# Battery_ECU.net
KiCad netlist of a schematic drawn in Altium Designer
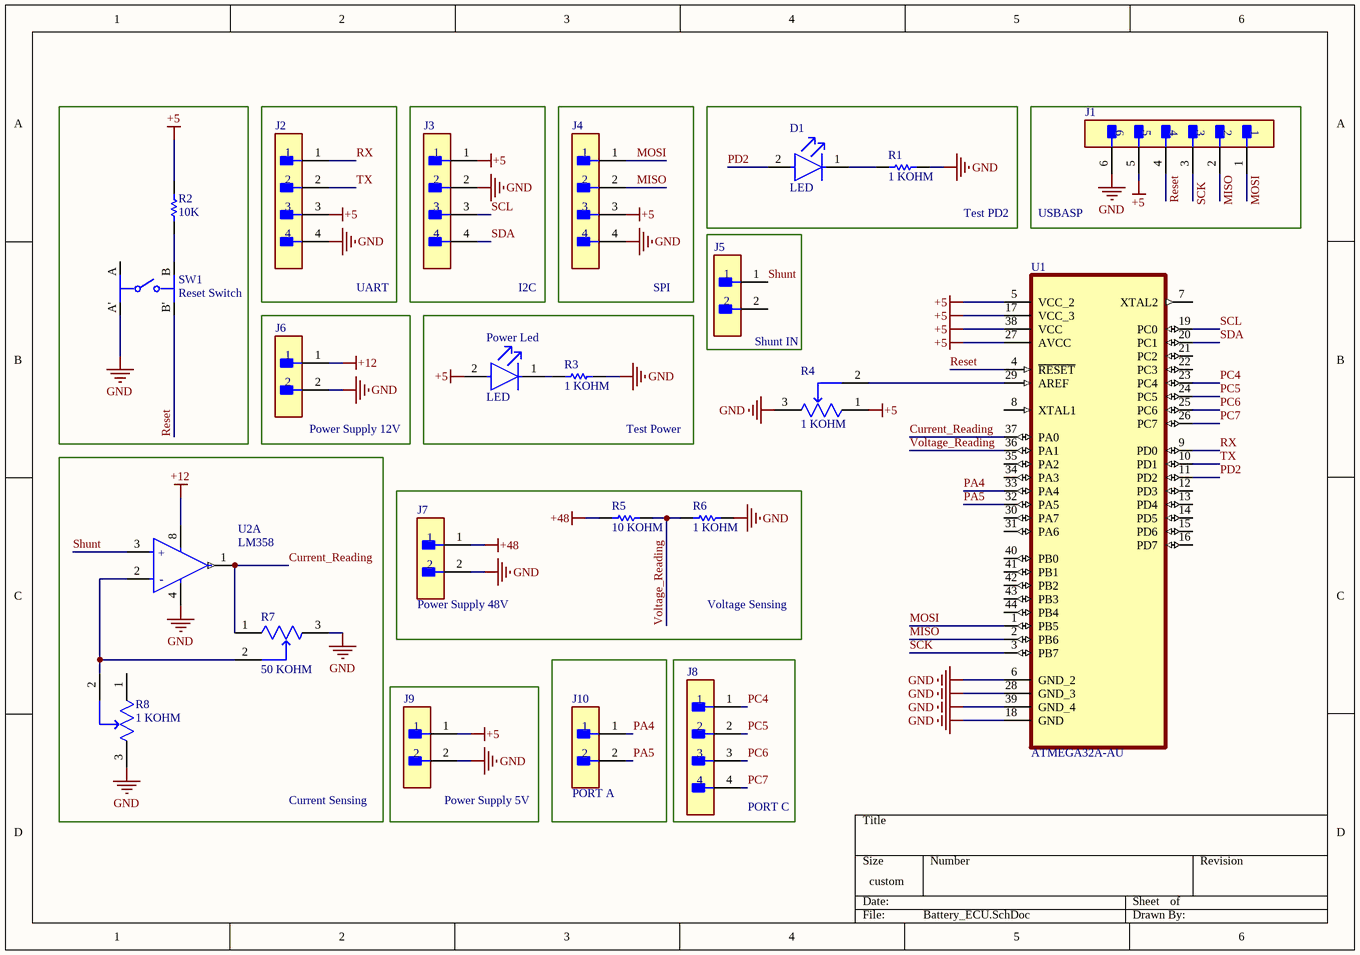
[diagram p0: Battery_ECU.SchDoc]

(export (version "E")
  (design (tool "Eeschema 10.0.6"))
  (components
    (comp (ref "D1")
      (value "LED")
      (footprint "FP-LTST-C171GKT-MFG")
      (description "LED GREEN CLEAR CHIP SMD")
      (libsource (lib "Altium Content Vault") (part "8706943c75ba83719d021d2fdc84c58"))
    )
    (comp (ref "J1")
      (value "USBASP")
      (footprint "FP-B6B-EH-A_LF_SN-MFG")
      (description "CONN HEADER VERT 6POS 2.5MM")
      (libsource (lib "Altium Content Vault") (part "f2cb566baf1c37ab5a3b8e90bbeafd6"))
    )
    (comp (ref "J2")
      (value "UART")
      (footprint "FP-B04B-XASK-1_LF_SN-MFG")
      (description "CONN HEADER VERT 4POS 2.5MM")
      (fields
        (field (name "OCTOPART") "https://octopart.com/b04b-xask-1%28lf%29%28sn%29-jst-3990149")
        (field (name "MANUFACTURER PART NUMBER") "B04B-XASK-1(LF)(SN)")
      )
      (libsource (lib "Altium Content Vault") (part "299a8cea1bdcbc3624fe62c390fa72c"))
    )
    (comp (ref "J3")
      (value "I2C")
      (footprint "FP-B04B-XASK-1_LF_SN-MFG")
      (description "CONN HEADER VERT 4POS 2.5MM")
      (fields
        (field (name "OCTOPART") "https://octopart.com/b04b-xask-1%28lf%29%28sn%29-jst-3990149")
        (field (name "MANUFACTURER PART NUMBER") "B04B-XASK-1(LF)(SN)")
      )
      (libsource (lib "Altium Content Vault") (part "299a8cea1bdcbc3624fe62c390fa72c"))
    )
    (comp (ref "J4")
      (value "SPI")
      (footprint "FP-B04B-XASK-1_LF_SN-MFG")
      (description "CONN HEADER VERT 4POS 2.5MM")
      (fields
        (field (name "OCTOPART") "https://octopart.com/b04b-xask-1%28lf%29%28sn%29-jst-3990149")
        (field (name "MANUFACTURER PART NUMBER") "B04B-XASK-1(LF)(SN)")
      )
      (libsource (lib "Altium Content Vault") (part "299a8cea1bdcbc3624fe62c390fa72c"))
    )
    (comp (ref "J5")
      (value "Shunt IN")
      (footprint "FP-B2B-XH-A_LF_SN-MFG")
      (description "CONN HEADER VERT 2POS 2.5MM")
      (libsource (lib "Altium Content Vault") (part "3bc925449376181038e59eaffc5286c"))
    )
    (comp (ref "J6")
      (value "Power Supply 12V")
      (footprint "FP-B2B-XH-A_LF_SN-MFG")
      (description "CONN HEADER VERT 2POS 2.5MM")
      (libsource (lib "Altium Content Vault") (part "3bc925449376181038e59eaffc5286c"))
    )
    (comp (ref "J7")
      (value "Power Supply 48V")
      (footprint "FP-B2B-XH-A_LF_SN-MFG")
      (description "CONN HEADER VERT 2POS 2.5MM")
      (libsource (lib "Altium Content Vault") (part "3bc925449376181038e59eaffc5286c"))
    )
    (comp (ref "J8")
      (value "PORT C")
      (footprint "FP-B04B-XASK-1_LF_SN-MFG")
      (description "CONN HEADER VERT 4POS 2.5MM")
      (fields
        (field (name "OCTOPART") "https://octopart.com/b04b-xask-1%28lf%29%28sn%29-jst-3990149")
        (field (name "MANUFACTURER PART NUMBER") "B04B-XASK-1(LF)(SN)")
      )
      (libsource (lib "Altium Content Vault") (part "299a8cea1bdcbc3624fe62c390fa72c"))
    )
    (comp (ref "J9")
      (value "Power Supply 5V")
      (footprint "FP-B2B-XH-A_LF_SN-MFG")
      (description "CONN HEADER VERT 2POS 2.5MM")
      (libsource (lib "Altium Content Vault") (part "3bc925449376181038e59eaffc5286c"))
    )
    (comp (ref "J10")
      (value "PORT A")
      (footprint "FP-B2B-XH-A_LF_SN-MFG")
      (description "CONN HEADER VERT 2POS 2.5MM")
      (libsource (lib "Altium Content Vault") (part "3bc925449376181038e59eaffc5286c"))
    )
    (comp (ref "Power Led")
      (value "LED")
      (footprint "FP-LTST-C171GKT-MFG")
      (description "LED GREEN CLEAR CHIP SMD")
      (libsource (lib "Altium Content Vault") (part "8706943c75ba83719d021d2fdc84c58"))
    )
    (comp (ref "R1")
      (value "1 KOHM")
      (footprint "RESC2013X60X35ML10T20")
      (fields (field (name "TOLERANCE") "5%") (field (name "MANUFACTURER") "Yageo"))
      (libsource (lib "Altium Content Vault") (part "RES-2"))
    )
    (comp (ref "R2")
      (value "10K")
      (footprint "RESC2013X60X35ML10T20")
      (fields (field (name "TOLERANCE") "5%") (field (name "MANUFACTURER") "Yageo"))
      (libsource (lib "Altium Content Vault") (part "RES-2"))
    )
    (comp (ref "R3")
      (value "1 KOHM")
      (footprint "RESC2013X60X35ML10T20")
      (fields (field (name "TOLERANCE") "5%") (field (name "MANUFACTURER") "Yageo"))
      (libsource (lib "Altium Content Vault") (part "RES-2"))
    )
    (comp (ref "R4")
      (value "1 KOHM")
      (footprint "FP-3296W-MFG")
      (description "TRIMMER 500K OHM 0.5W PC PIN TOP")
      (fields
        (field (name "MANUFACTURER") "Bourns")
        (field (name "OCTOPART") "https://octopart.com/3296w-1-504lf-bourns-143884")
      )
      (libsource (lib "Altium Content Vault") (part "8d460c8a6f7ec10b1759d1b9c49aa93"))
    )
    (comp (ref "R5")
      (value "10 KOHM")
      (footprint "RESC2013X60X35ML10T20")
      (fields (field (name "TOLERANCE") "5%") (field (name "MANUFACTURER") "Yageo"))
      (libsource (lib "Altium Content Vault") (part "RES-2"))
    )
    (comp (ref "R6")
      (value "1 KOHM")
      (footprint "RESC2013X60X35ML10T20")
      (fields (field (name "TOLERANCE") "5%") (field (name "MANUFACTURER") "Yageo"))
      (libsource (lib "Altium Content Vault") (part "RES-2"))
    )
    (comp (ref "R7")
      (value "50 KOHM")
      (footprint "FP-3296W-MFG")
      (description "TRIMMER 500K OHM 0.5W PC PIN TOP")
      (fields
        (field (name "MANUFACTURER") "Bourns")
        (field (name "OCTOPART") "https://octopart.com/3296w-1-504lf-bourns-143884")
      )
      (libsource (lib "Altium Content Vault") (part "8d460c8a6f7ec10b1759d1b9c49aa93"))
    )
    (comp (ref "R8")
      (value "1 KOHM")
      (footprint "FP-3296W-MFG")
      (description "TRIMMER 500K OHM 0.5W PC PIN TOP")
      (fields
        (field (name "MANUFACTURER") "Bourns")
        (field (name "OCTOPART") "https://octopart.com/3296w-1-504lf-bourns-143884")
      )
      (libsource (lib "Altium Content Vault") (part "8d460c8a6f7ec10b1759d1b9c49aa93"))
    )
    (comp (ref "SW1")
      (value "Reset Switch")
      (footprint "FP-EVQQ2Y02W-MFG")
      (description "SWITCH TACTILE SPST-NO 0.02A 15V")
      (libsource (lib "Altium Content Vault") (part "841f23923f71b23f3ea0ab5dfb78dcc"))
    )
    (comp (ref "U1")
      (value "ATMEGA32A-AU")
      (footprint "QFP80P1200X1200X120-44N")
      (description "AVR AVRÂ® ATmega Microcontroller IC 8-Bit 16MHz 32KB (16K x 16) FLASH 44-TQFP (10x10)")
      (fields (field (name "MF") "Microchip"))
      (libsource (lib "ATMEGA32A-AU") (part "ATMEGA32A-AU"))
    )
    (comp (ref "U2")
      (value "LM358")
      (footprint "FP-751-07-IPC_C")
      (description "IC OPAMP GP 2 CIRCUIT 8SOIC")
      (libsource (lib "Altium Content Vault") (part "992a6607d1d88c80ee6b45e5ba6cb1b"))
    )
  )
  (nets
    (net (code "1") (name "+5") (class "Default")
      (node (ref "J1") (pin "5") (pinfunction "5_5") (pintype "passive"))
      (node (ref "J2") (pin "3") (pinfunction "3_3") (pintype "passive"))
      (node (ref "J3") (pin "1") (pinfunction "1_1") (pintype "passive"))
      (node (ref "J4") (pin "3") (pinfunction "3_3") (pintype "passive"))
      (node (ref "J9") (pin "1") (pinfunction "1_1") (pintype "passive"))
      (node (ref "Power Led") (pin "2") (pinfunction "A_2") (pintype "passive"))
      (node (ref "R2") (pin "2") (pinfunction "2_2") (pintype "passive"))
      (node (ref "R4") (pin "1") (pinfunction "CCW_1") (pintype "passive"))
      (node (ref "U1") (pin "17") (pinfunction "VCC_3_17") (pintype "power_in"))
      (node (ref "U1") (pin "27") (pinfunction "AVCC_27") (pintype "power_in"))
      (node (ref "U1") (pin "38") (pinfunction "VCC_38") (pintype "power_in"))
      (node (ref "U1") (pin "5") (pinfunction "VCC_2_5") (pintype "power_in"))
    )
    (net (code "2") (name "+12") (class "Default")
      (node (ref "J6") (pin "1") (pinfunction "1_1") (pintype "passive"))
      (node (ref "U2") (pin "8") (pinfunction "VCC_8") (pintype "power_in"))
    )
    (net (code "3") (name "+48") (class "Default")
      (node (ref "J7") (pin "1") (pinfunction "1_1") (pintype "passive"))
      (node (ref "R5") (pin "2") (pinfunction "2_2") (pintype "passive"))
    )
    (net (code "4") (name "/Current_Reading") (class "Default")
      (node (ref "R7") (pin "1") (pinfunction "CCW_1") (pintype "passive"))
      (node (ref "U1") (pin "37") (pinfunction "PA0_37") (pintype "bidirectional"))
      (node (ref "U2") (pin "1") (pinfunction "OUTPUT_A_1") (pintype "output"))
    )
    (net (code "5") (name "/MISO") (class "Default")
      (node (ref "J1") (pin "2") (pinfunction "2_2") (pintype "passive"))
      (node (ref "J4") (pin "2") (pinfunction "2_2") (pintype "passive"))
      (node (ref "U1") (pin "2") (pinfunction "PB6_2") (pintype "bidirectional"))
    )
    (net (code "6") (name "/MOSI") (class "Default")
      (node (ref "J1") (pin "1") (pinfunction "1_1") (pintype "passive"))
      (node (ref "J4") (pin "1") (pinfunction "1_1") (pintype "passive"))
      (node (ref "U1") (pin "1") (pinfunction "PB5_1") (pintype "bidirectional"))
    )
    (net (code "7") (name "/PA4") (class "Default")
      (node (ref "J10") (pin "1") (pinfunction "1_1") (pintype "passive"))
      (node (ref "U1") (pin "33") (pinfunction "PA4_33") (pintype "bidirectional"))
    )
    (net (code "8") (name "/PA5") (class "Default")
      (node (ref "J10") (pin "2") (pinfunction "2_2") (pintype "passive"))
      (node (ref "U1") (pin "32") (pinfunction "PA5_32") (pintype "bidirectional"))
    )
    (net (code "9") (name "/PC4") (class "Default")
      (node (ref "J8") (pin "1") (pinfunction "1_1") (pintype "passive"))
      (node (ref "U1") (pin "23") (pinfunction "PC4_23") (pintype "bidirectional"))
    )
    (net (code "10") (name "/PC5") (class "Default")
      (node (ref "J8") (pin "2") (pinfunction "2_2") (pintype "passive"))
      (node (ref "U1") (pin "24") (pinfunction "PC5_24") (pintype "bidirectional"))
    )
    (net (code "11") (name "/PC6") (class "Default")
      (node (ref "J8") (pin "3") (pinfunction "3_3") (pintype "passive"))
      (node (ref "U1") (pin "25") (pinfunction "PC6_25") (pintype "bidirectional"))
    )
    (net (code "12") (name "/PC7") (class "Default")
      (node (ref "J8") (pin "4") (pinfunction "4_4") (pintype "passive"))
      (node (ref "U1") (pin "26") (pinfunction "PC7_26") (pintype "bidirectional"))
    )
    (net (code "13") (name "/PD2") (class "Default")
      (node (ref "D1") (pin "2") (pinfunction "A_2") (pintype "passive"))
      (node (ref "U1") (pin "11") (pinfunction "PD2_11") (pintype "bidirectional"))
    )
    (net (code "14") (name "/RX") (class "Default")
      (node (ref "J2") (pin "1") (pinfunction "1_1") (pintype "passive"))
      (node (ref "U1") (pin "9") (pinfunction "PD0_9") (pintype "bidirectional"))
    )
    (net (code "15") (name "/Reset") (class "Default")
      (node (ref "J1") (pin "4") (pinfunction "4_4") (pintype "passive"))
      (node (ref "SW1") (pin "B'") (pinfunction "B'_B'") (pintype "passive"))
      (node (ref "U1") (pin "4") (pinfunction "~{RESET}_4") (pintype "input"))
    )
    (net (code "16") (name "/SCK") (class "Default")
      (node (ref "J1") (pin "3") (pinfunction "3_3") (pintype "passive"))
      (node (ref "U1") (pin "3") (pinfunction "PB7_3") (pintype "bidirectional"))
    )
    (net (code "17") (name "/SCL") (class "Default")
      (node (ref "J3") (pin "3") (pinfunction "3_3") (pintype "passive"))
      (node (ref "U1") (pin "19") (pinfunction "PC0_19") (pintype "bidirectional"))
    )
    (net (code "18") (name "/SDA") (class "Default")
      (node (ref "J3") (pin "4") (pinfunction "4_4") (pintype "passive"))
      (node (ref "U1") (pin "20") (pinfunction "PC1_20") (pintype "bidirectional"))
    )
    (net (code "19") (name "/Shunt") (class "Default")
      (node (ref "J5") (pin "1") (pinfunction "1_1") (pintype "passive"))
      (node (ref "U2") (pin "3") (pinfunction "INPUT_A+_3") (pintype "tri_state"))
    )
    (net (code "20") (name "/TX") (class "Default")
      (node (ref "J2") (pin "2") (pinfunction "2_2") (pintype "passive"))
      (node (ref "U1") (pin "10") (pinfunction "PD1_10") (pintype "bidirectional"))
    )
    (net (code "21") (name "/Voltage_Reading") (class "Default")
      (node (ref "R5") (pin "1") (pinfunction "1_1") (pintype "passive"))
      (node (ref "R6") (pin "2") (pinfunction "2_2") (pintype "passive"))
      (node (ref "U1") (pin "36") (pinfunction "PA1_36") (pintype "bidirectional"))
    )
    (net (code "22") (name "GND") (class "Default")
      (node (ref "J1") (pin "6") (pinfunction "6_6") (pintype "passive"))
      (node (ref "J2") (pin "4") (pinfunction "4_4") (pintype "passive"))
      (node (ref "J3") (pin "2") (pinfunction "2_2") (pintype "passive"))
      (node (ref "J4") (pin "4") (pinfunction "4_4") (pintype "passive"))
      (node (ref "J6") (pin "2") (pinfunction "2_2") (pintype "passive"))
      (node (ref "J7") (pin "2") (pinfunction "2_2") (pintype "passive"))
      (node (ref "J9") (pin "2") (pinfunction "2_2") (pintype "passive"))
      (node (ref "R1") (pin "2") (pinfunction "2_2") (pintype "passive"))
      (node (ref "R3") (pin "2") (pinfunction "2_2") (pintype "passive"))
      (node (ref "R4") (pin "3") (pinfunction "CW_3") (pintype "passive"))
      (node (ref "R6") (pin "1") (pinfunction "1_1") (pintype "passive"))
      (node (ref "R7") (pin "3") (pinfunction "CW_3") (pintype "passive"))
      (node (ref "R8") (pin "3") (pinfunction "CW_3") (pintype "passive"))
      (node (ref "SW1") (pin "A'") (pinfunction "A'_A'") (pintype "passive"))
      (node (ref "U1") (pin "18") (pinfunction "GND_18") (pintype "passive"))
      (node (ref "U1") (pin "28") (pinfunction "GND_3_28") (pintype "passive"))
      (node (ref "U1") (pin "39") (pinfunction "GND_4_39") (pintype "passive"))
      (node (ref "U1") (pin "6") (pinfunction "GND_2_6") (pintype "passive"))
      (node (ref "U2") (pin "4") (pinfunction "VEE/GND_4") (pintype "power_in"))
    )
    (net (code "23") (name "Net-(D1-C)") (class "Default")
      (node (ref "D1") (pin "1") (pinfunction "C_1") (pintype "passive"))
      (node (ref "R1") (pin "1") (pinfunction "1_1") (pintype "passive"))
    )
    (net (code "24") (name "Net-(Power Led-C)") (class "Default")
      (node (ref "Power Led") (pin "1") (pinfunction "C_1") (pintype "passive"))
      (node (ref "R3") (pin "1") (pinfunction "1_1") (pintype "passive"))
    )
    (net (code "25") (name "Net-(R2-Pad1)") (class "Default")
      (node (ref "R2") (pin "1") (pinfunction "1_1") (pintype "passive"))
      (node (ref "SW1") (pin "B") (pinfunction "B_B") (pintype "passive"))
    )
    (net (code "26") (name "Net-(R4-WIPER)") (class "Default")
      (node (ref "R4") (pin "2") (pinfunction "WIPER_2") (pintype "passive"))
      (node (ref "U1") (pin "29") (pinfunction "AREF_29") (pintype "input"))
    )
    (net (code "27") (name "Net-(R7-WIPER)") (class "Default")
      (node (ref "R7") (pin "2") (pinfunction "WIPER_2") (pintype "passive"))
      (node (ref "R8") (pin "2") (pinfunction "WIPER_2") (pintype "passive"))
      (node (ref "U2") (pin "2") (pinfunction "INPUT_A-_2") (pintype "tri_state"))
    )
    (net (code "28") (name "unconnected-(J5-Pad2)") (class "Default")
      (node (ref "J5") (pin "2") (pinfunction "2_2") (pintype "passive"))
    )
    (net (code "29") (name "unconnected-(R8-CCW-Pad1)") (class "Default")
      (node (ref "R8") (pin "1") (pinfunction "CCW_1") (pintype "passive"))
    )
    (net (code "30") (name "unconnected-(SW1-PadA)") (class "Default")
      (node (ref "SW1") (pin "A") (pinfunction "A_A") (pintype "passive"))
    )
    (net (code "31") (name "unconnected-(U1-PA2-Pad35)") (class "Default")
      (node (ref "U1") (pin "35") (pinfunction "PA2_35") (pintype "bidirectional"))
    )
    (net (code "32") (name "unconnected-(U1-PA3-Pad34)") (class "Default")
      (node (ref "U1") (pin "34") (pinfunction "PA3_34") (pintype "bidirectional"))
    )
    (net (code "33") (name "unconnected-(U1-PA6-Pad31)") (class "Default")
      (node (ref "U1") (pin "31") (pinfunction "PA6_31") (pintype "bidirectional"))
    )
    (net (code "34") (name "unconnected-(U1-PA7-Pad30)") (class "Default")
      (node (ref "U1") (pin "30") (pinfunction "PA7_30") (pintype "bidirectional"))
    )
    (net (code "35") (name "unconnected-(U1-PB0-Pad40)") (class "Default")
      (node (ref "U1") (pin "40") (pinfunction "PB0_40") (pintype "bidirectional"))
    )
    (net (code "36") (name "unconnected-(U1-PB1-Pad41)") (class "Default")
      (node (ref "U1") (pin "41") (pinfunction "PB1_41") (pintype "bidirectional"))
    )
    (net (code "37") (name "unconnected-(U1-PB2-Pad42)") (class "Default")
      (node (ref "U1") (pin "42") (pinfunction "PB2_42") (pintype "bidirectional"))
    )
    (net (code "38") (name "unconnected-(U1-PB3-Pad43)") (class "Default")
      (node (ref "U1") (pin "43") (pinfunction "PB3_43") (pintype "bidirectional"))
    )
    (net (code "39") (name "unconnected-(U1-PB4-Pad44)") (class "Default")
      (node (ref "U1") (pin "44") (pinfunction "PB4_44") (pintype "bidirectional"))
    )
    (net (code "40") (name "unconnected-(U1-PC2-Pad21)") (class "Default")
      (node (ref "U1") (pin "21") (pinfunction "PC2_21") (pintype "bidirectional"))
    )
    (net (code "41") (name "unconnected-(U1-PC3-Pad22)") (class "Default")
      (node (ref "U1") (pin "22") (pinfunction "PC3_22") (pintype "bidirectional"))
    )
    (net (code "42") (name "unconnected-(U1-PD3-Pad12)") (class "Default")
      (node (ref "U1") (pin "12") (pinfunction "PD3_12") (pintype "bidirectional"))
    )
    (net (code "43") (name "unconnected-(U1-PD4-Pad13)") (class "Default")
      (node (ref "U1") (pin "13") (pinfunction "PD4_13") (pintype "bidirectional"))
    )
    (net (code "44") (name "unconnected-(U1-PD5-Pad14)") (class "Default")
      (node (ref "U1") (pin "14") (pinfunction "PD5_14") (pintype "bidirectional"))
    )
    (net (code "45") (name "unconnected-(U1-PD6-Pad15)") (class "Default")
      (node (ref "U1") (pin "15") (pinfunction "PD6_15") (pintype "bidirectional"))
    )
    (net (code "46") (name "unconnected-(U1-PD7-Pad16)") (class "Default")
      (node (ref "U1") (pin "16") (pinfunction "PD7_16") (pintype "bidirectional"))
    )
    (net (code "47") (name "unconnected-(U1-XTAL1-Pad8)") (class "Default")
      (node (ref "U1") (pin "8") (pinfunction "XTAL1_8") (pintype "input"))
    )
    (net (code "48") (name "unconnected-(U1-XTAL2-Pad7)") (class "Default")
      (node (ref "U1") (pin "7") (pinfunction "XTAL2_7") (pintype "output"))
    )
  )
)
